# Opto.net
KiCad netlist of a schematic drawn in Altium Designer
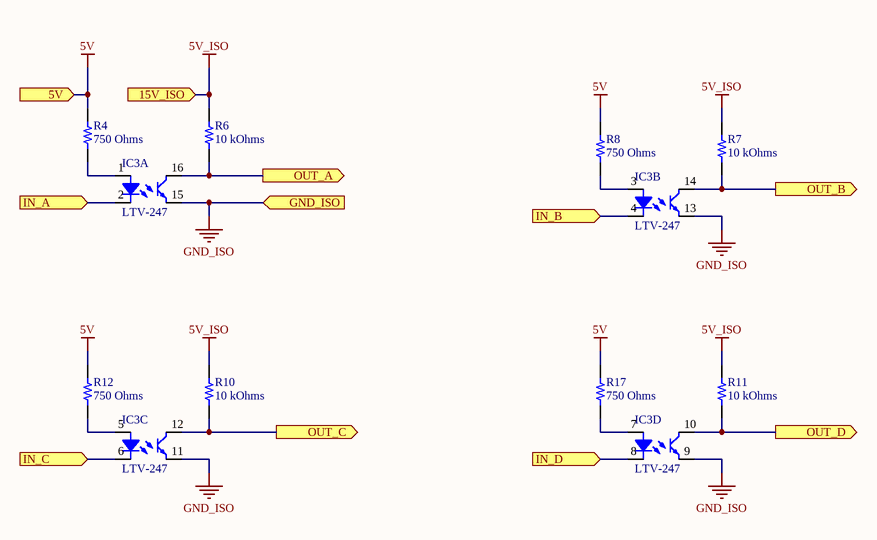
[diagram p0: Opto.SchDoc]

(export (version "E")
  (design (tool "Eeschema 10.0.6"))
  (components
    (comp (ref "IC3")
      (value "LTV-247")
      (footprint "LITEON SOIC-16 LTV-247")
      (description "OPTOISO 3.75KV 4CH TRANS 16SO")
      (fields (field (name "MANUFACTURER") "Lite-On Inc."))
      (libsource (lib "altiumlibrary.com") (part "LITEON LTV-247"))
    )
    (comp (ref "R4")
      (value "750 Ohms")
      (footprint "RES 0603_1608")
      (description "RES 750 OHM 1% 1/10W 0603")
      (fields
        (field (name "PART NUMBER") "RMCF0603FT750R")
        (field (name "MANUFACTURER") "Stackpole Electronics Inc")
      )
      (libsource (lib "altiumlibrary.com") (part "Resistor"))
    )
    (comp (ref "R6")
      (value "10 kOhms")
      (footprint "RES 0603_1608")
      (description "RES 10K OHM 1% 1/5W 0603")
      (fields
        (field (name "PART NUMBER") "SG73S1JTTD1002F")
        (field (name "MANUFACTURER") "KOA Speer Electronics, Inc.")
      )
      (libsource (lib "altiumlibrary.com") (part "Resistor"))
    )
    (comp (ref "R7")
      (value "10 kOhms")
      (footprint "RES 0603_1608")
      (description "RES 10K OHM 1% 1/5W 0603")
      (fields
        (field (name "PART NUMBER") "SG73S1JTTD1002F")
        (field (name "MANUFACTURER") "KOA Speer Electronics, Inc.")
      )
      (libsource (lib "altiumlibrary.com") (part "Resistor"))
    )
    (comp (ref "R8")
      (value "750 Ohms")
      (footprint "RES 0603_1608")
      (description "RES 750 OHM 1% 1/10W 0603")
      (fields
        (field (name "PART NUMBER") "RMCF0603FT750R")
        (field (name "MANUFACTURER") "Stackpole Electronics Inc")
      )
      (libsource (lib "altiumlibrary.com") (part "Resistor"))
    )
    (comp (ref "R10")
      (value "10 kOhms")
      (footprint "RES 0603_1608")
      (description "RES 10K OHM 1% 1/5W 0603")
      (fields
        (field (name "PART NUMBER") "SG73S1JTTD1002F")
        (field (name "MANUFACTURER") "KOA Speer Electronics, Inc.")
      )
      (libsource (lib "altiumlibrary.com") (part "Resistor"))
    )
    (comp (ref "R11")
      (value "10 kOhms")
      (footprint "RES 0603_1608")
      (description "RES 10K OHM 1% 1/5W 0603")
      (fields
        (field (name "PART NUMBER") "SG73S1JTTD1002F")
        (field (name "MANUFACTURER") "KOA Speer Electronics, Inc.")
      )
      (libsource (lib "altiumlibrary.com") (part "Resistor"))
    )
    (comp (ref "R12")
      (value "750 Ohms")
      (footprint "RES 0603_1608")
      (description "RES 750 OHM 1% 1/10W 0603")
      (fields
        (field (name "PART NUMBER") "RMCF0603FT750R")
        (field (name "MANUFACTURER") "Stackpole Electronics Inc")
      )
      (libsource (lib "altiumlibrary.com") (part "Resistor"))
    )
    (comp (ref "R17")
      (value "750 Ohms")
      (footprint "RES 0603_1608")
      (description "RES 750 OHM 1% 1/10W 0603")
      (fields
        (field (name "PART NUMBER") "RMCF0603FT750R")
        (field (name "MANUFACTURER") "Stackpole Electronics Inc")
      )
      (libsource (lib "altiumlibrary.com") (part "Resistor"))
    )
  )
  (nets
    (net (code "1") (name "/IN_A") (class "Default")
      (node (ref "IC3") (pin "2") (pinfunction "2_2") (pintype "passive"))
    )
    (net (code "2") (name "/IN_B") (class "Default")
      (node (ref "IC3") (pin "4") (pinfunction "4_4") (pintype "passive"))
    )
    (net (code "3") (name "/IN_C") (class "Default")
      (node (ref "IC3") (pin "6") (pinfunction "6_6") (pintype "passive"))
    )
    (net (code "4") (name "/IN_D") (class "Default")
      (node (ref "IC3") (pin "8") (pinfunction "8_8") (pintype "passive"))
    )
    (net (code "5") (name "/OUT_A") (class "Default")
      (node (ref "IC3") (pin "16") (pinfunction "16_16") (pintype "passive"))
      (node (ref "R6") (pin "1") (pinfunction "1_1") (pintype "passive"))
    )
    (net (code "6") (name "/OUT_B") (class "Default")
      (node (ref "IC3") (pin "14") (pinfunction "14_14") (pintype "passive"))
      (node (ref "R7") (pin "1") (pinfunction "1_1") (pintype "passive"))
    )
    (net (code "7") (name "/OUT_C") (class "Default")
      (node (ref "IC3") (pin "12") (pinfunction "12_12") (pintype "passive"))
      (node (ref "R10") (pin "1") (pinfunction "1_1") (pintype "passive"))
    )
    (net (code "8") (name "/OUT_D") (class "Default")
      (node (ref "IC3") (pin "10") (pinfunction "10_10") (pintype "passive"))
      (node (ref "R11") (pin "1") (pinfunction "1_1") (pintype "passive"))
    )
    (net (code "9") (name "5V") (class "Default")
      (node (ref "R12") (pin "1") (pinfunction "1_1") (pintype "passive"))
      (node (ref "R17") (pin "1") (pinfunction "1_1") (pintype "passive"))
      (node (ref "R4") (pin "2") (pinfunction "2_2") (pintype "passive"))
      (node (ref "R8") (pin "2") (pinfunction "2_2") (pintype "passive"))
    )
    (net (code "10") (name "5V_ISO") (class "Default")
      (node (ref "R10") (pin "2") (pinfunction "2_2") (pintype "passive"))
      (node (ref "R11") (pin "2") (pinfunction "2_2") (pintype "passive"))
      (node (ref "R6") (pin "2") (pinfunction "2_2") (pintype "passive"))
      (node (ref "R7") (pin "2") (pinfunction "2_2") (pintype "passive"))
    )
    (net (code "11") (name "GND_ISO") (class "Default")
      (node (ref "IC3") (pin "11") (pinfunction "11_11") (pintype "passive"))
      (node (ref "IC3") (pin "13") (pinfunction "13_13") (pintype "passive"))
      (node (ref "IC3") (pin "15") (pinfunction "15_15") (pintype "passive"))
      (node (ref "IC3") (pin "9") (pinfunction "9_9") (pintype "passive"))
    )
    (net (code "12") (name "Net-(IC3-Pad1)") (class "Default")
      (node (ref "IC3") (pin "1") (pinfunction "1_1") (pintype "passive"))
      (node (ref "R4") (pin "1") (pinfunction "1_1") (pintype "passive"))
    )
    (net (code "13") (name "Net-(IC3-Pad3)") (class "Default")
      (node (ref "IC3") (pin "3") (pinfunction "3_3") (pintype "passive"))
      (node (ref "R8") (pin "1") (pinfunction "1_1") (pintype "passive"))
    )
    (net (code "14") (name "Net-(IC3-Pad5)") (class "Default")
      (node (ref "IC3") (pin "5") (pinfunction "5_5") (pintype "passive"))
      (node (ref "R12") (pin "2") (pinfunction "2_2") (pintype "passive"))
    )
    (net (code "15") (name "Net-(IC3-Pad7)") (class "Default")
      (node (ref "IC3") (pin "7") (pinfunction "7_7") (pintype "passive"))
      (node (ref "R17") (pin "2") (pinfunction "2_2") (pintype "passive"))
    )
  )
)
